# Bipolar_5v_Power_Supply_V1_0.net
KiCad netlist of a schematic drawn in EAGLE
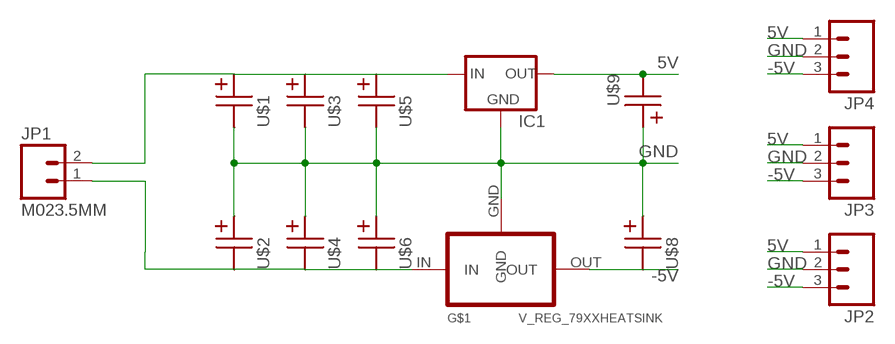
[diagram p0: schematic, sheet 1]

(export (version "E")
  (design (tool "Eeschema 10.0.6"))
  (components
    (comp (ref "IC1")
      (value "V_REG_78XXSINK")
      (footprint "eagle-import:TO220-IGO")
      (libsource (lib "eagle-import") (part "V_REG_78XXSINK"))
    )
    (comp (ref "JP1")
      (value "M023.5MM")
      (footprint "eagle-import:SCREWTERMINAL-3.5MM-2")
      (libsource (lib "eagle-import") (part "M023.5MM"))
    )
    (comp (ref "JP2")
      (value "M03SCREW")
      (footprint "eagle-import:SCREWTERMINAL-3.5MM-3")
      (libsource (lib "eagle-import") (part "M03SCREW"))
    )
    (comp (ref "JP3")
      (value "M03SCREW")
      (footprint "eagle-import:SCREWTERMINAL-3.5MM-3")
      (libsource (lib "eagle-import") (part "M03SCREW"))
    )
    (comp (ref "JP4")
      (value "M03SCREW")
      (footprint "eagle-import:SCREWTERMINAL-3.5MM-3")
      (libsource (lib "eagle-import") (part "M03SCREW"))
    )
    (comp (ref "U$1")
      (value "5MM-12.5MM-POLAR5MMX12.5MM")
      (footprint "eagle-import:5MMLEAD_12.5MMDIAMETER")
      (libsource (lib "eagle-import") (part "5MM-12.5MM-POLAR5MMX12.5MM"))
    )
    (comp (ref "U$2")
      (value "5MM-12.5MM-POLAR5MMX12.5MM")
      (footprint "eagle-import:5MMLEAD_12.5MMDIAMETER")
      (libsource (lib "eagle-import") (part "5MM-12.5MM-POLAR5MMX12.5MM"))
    )
    (comp (ref "U$3")
      (value "5MM-12.5MM-POLAR5MMX12.5MM")
      (footprint "eagle-import:5MMLEAD_12.5MMDIAMETER")
      (libsource (lib "eagle-import") (part "5MM-12.5MM-POLAR5MMX12.5MM"))
    )
    (comp (ref "U$4")
      (value "5MM-12.5MM-POLAR5MMX12.5MM")
      (footprint "eagle-import:5MMLEAD_12.5MMDIAMETER")
      (libsource (lib "eagle-import") (part "5MM-12.5MM-POLAR5MMX12.5MM"))
    )
    (comp (ref "U$5")
      (value "5MM-12.5MM-POLAR5MMX12.5MM")
      (footprint "eagle-import:5MMLEAD_12.5MMDIAMETER")
      (libsource (lib "eagle-import") (part "5MM-12.5MM-POLAR5MMX12.5MM"))
    )
    (comp (ref "U$6")
      (value "5MM-12.5MM-POLAR5MMX12.5MM")
      (footprint "eagle-import:5MMLEAD_12.5MMDIAMETER")
      (libsource (lib "eagle-import") (part "5MM-12.5MM-POLAR5MMX12.5MM"))
    )
    (comp (ref "U$7")
      (value "V_REG_79XXHEATSINK")
      (footprint "eagle-import:TO220-IGO")
      (libsource (lib "eagle-import") (part "V_REG_79XXHEATSINK"))
    )
    (comp (ref "U$8")
      (value "5MM-12.5MM-POLAR2MMX5MM")
      (footprint "eagle-import:2MMLEAD_5MMDIAMETER")
      (libsource (lib "eagle-import") (part "5MM-12.5MM-POLAR2MMX5MM"))
    )
    (comp (ref "U$9")
      (value "5MM-12.5MM-POLAR2MMX5MM")
      (footprint "eagle-import:2MMLEAD_5MMDIAMETER")
      (libsource (lib "eagle-import") (part "5MM-12.5MM-POLAR2MMX5MM"))
    )
  )
  (nets
    (net (code "1") (name "/-5V") (class "Default")
      (node (ref "JP2") (pin "3") (pinfunction "3_3") (pintype "passive"))
      (node (ref "JP3") (pin "3") (pinfunction "3_3") (pintype "passive"))
      (node (ref "JP4") (pin "3") (pinfunction "3_3") (pintype "passive"))
      (node (ref "U$7") (pin "OUT") (pinfunction "OUT_OUT") (pintype "bidirectional"))
      (node (ref "U$8") (pin "+") (pinfunction "-_+") (pintype "bidirectional"))
    )
    (net (code "2") (name "/5V") (class "Default")
      (node (ref "IC1") (pin "OUT") (pinfunction "OUT_OUT") (pintype "output"))
      (node (ref "JP2") (pin "1") (pinfunction "1_1") (pintype "passive"))
      (node (ref "JP3") (pin "1") (pinfunction "1_1") (pintype "passive"))
      (node (ref "JP4") (pin "1") (pinfunction "1_1") (pintype "passive"))
      (node (ref "U$9") (pin "+") (pinfunction "-_+") (pintype "bidirectional"))
    )
    (net (code "3") (name "/GND") (class "Default")
      (node (ref "IC1") (pin "GND") (pinfunction "GND_GND") (pintype "input"))
      (node (ref "JP2") (pin "2") (pinfunction "2_2") (pintype "passive"))
      (node (ref "JP3") (pin "2") (pinfunction "2_2") (pintype "passive"))
      (node (ref "JP4") (pin "2") (pinfunction "2_2") (pintype "passive"))
      (node (ref "U$1") (pin "+") (pinfunction "-_+") (pintype "bidirectional"))
      (node (ref "U$2") (pin "-") (pinfunction "+_-") (pintype "bidirectional"))
      (node (ref "U$3") (pin "+") (pinfunction "-_+") (pintype "bidirectional"))
      (node (ref "U$4") (pin "-") (pinfunction "+_-") (pintype "bidirectional"))
      (node (ref "U$5") (pin "+") (pinfunction "-_+") (pintype "bidirectional"))
      (node (ref "U$6") (pin "-") (pinfunction "+_-") (pintype "bidirectional"))
      (node (ref "U$7") (pin "GND") (pinfunction "GND_GND") (pintype "bidirectional"))
      (node (ref "U$8") (pin "-") (pinfunction "+_-") (pintype "bidirectional"))
      (node (ref "U$9") (pin "-") (pinfunction "+_-") (pintype "bidirectional"))
    )
    (net (code "4") (name "Net-(U$1-+)") (class "Default")
      (node (ref "IC1") (pin "IN") (pinfunction "IN_IN") (pintype "input"))
      (node (ref "JP1") (pin "2") (pinfunction "2_2") (pintype "passive"))
      (node (ref "U$1") (pin "-") (pinfunction "+_-") (pintype "bidirectional"))
      (node (ref "U$3") (pin "-") (pinfunction "+_-") (pintype "bidirectional"))
      (node (ref "U$5") (pin "-") (pinfunction "+_-") (pintype "bidirectional"))
    )
    (net (code "5") (name "Net-(U$2--)") (class "Default")
      (node (ref "JP1") (pin "1") (pinfunction "1_1") (pintype "passive"))
      (node (ref "U$2") (pin "+") (pinfunction "-_+") (pintype "bidirectional"))
      (node (ref "U$4") (pin "+") (pinfunction "-_+") (pintype "bidirectional"))
      (node (ref "U$6") (pin "+") (pinfunction "-_+") (pintype "bidirectional"))
      (node (ref "U$7") (pin "IN") (pinfunction "IN_IN") (pintype "bidirectional"))
    )
  )
)
